# ODGIRON-v1_0-F4x1-0412.net
KiCad netlist of a schematic drawn in EAGLE
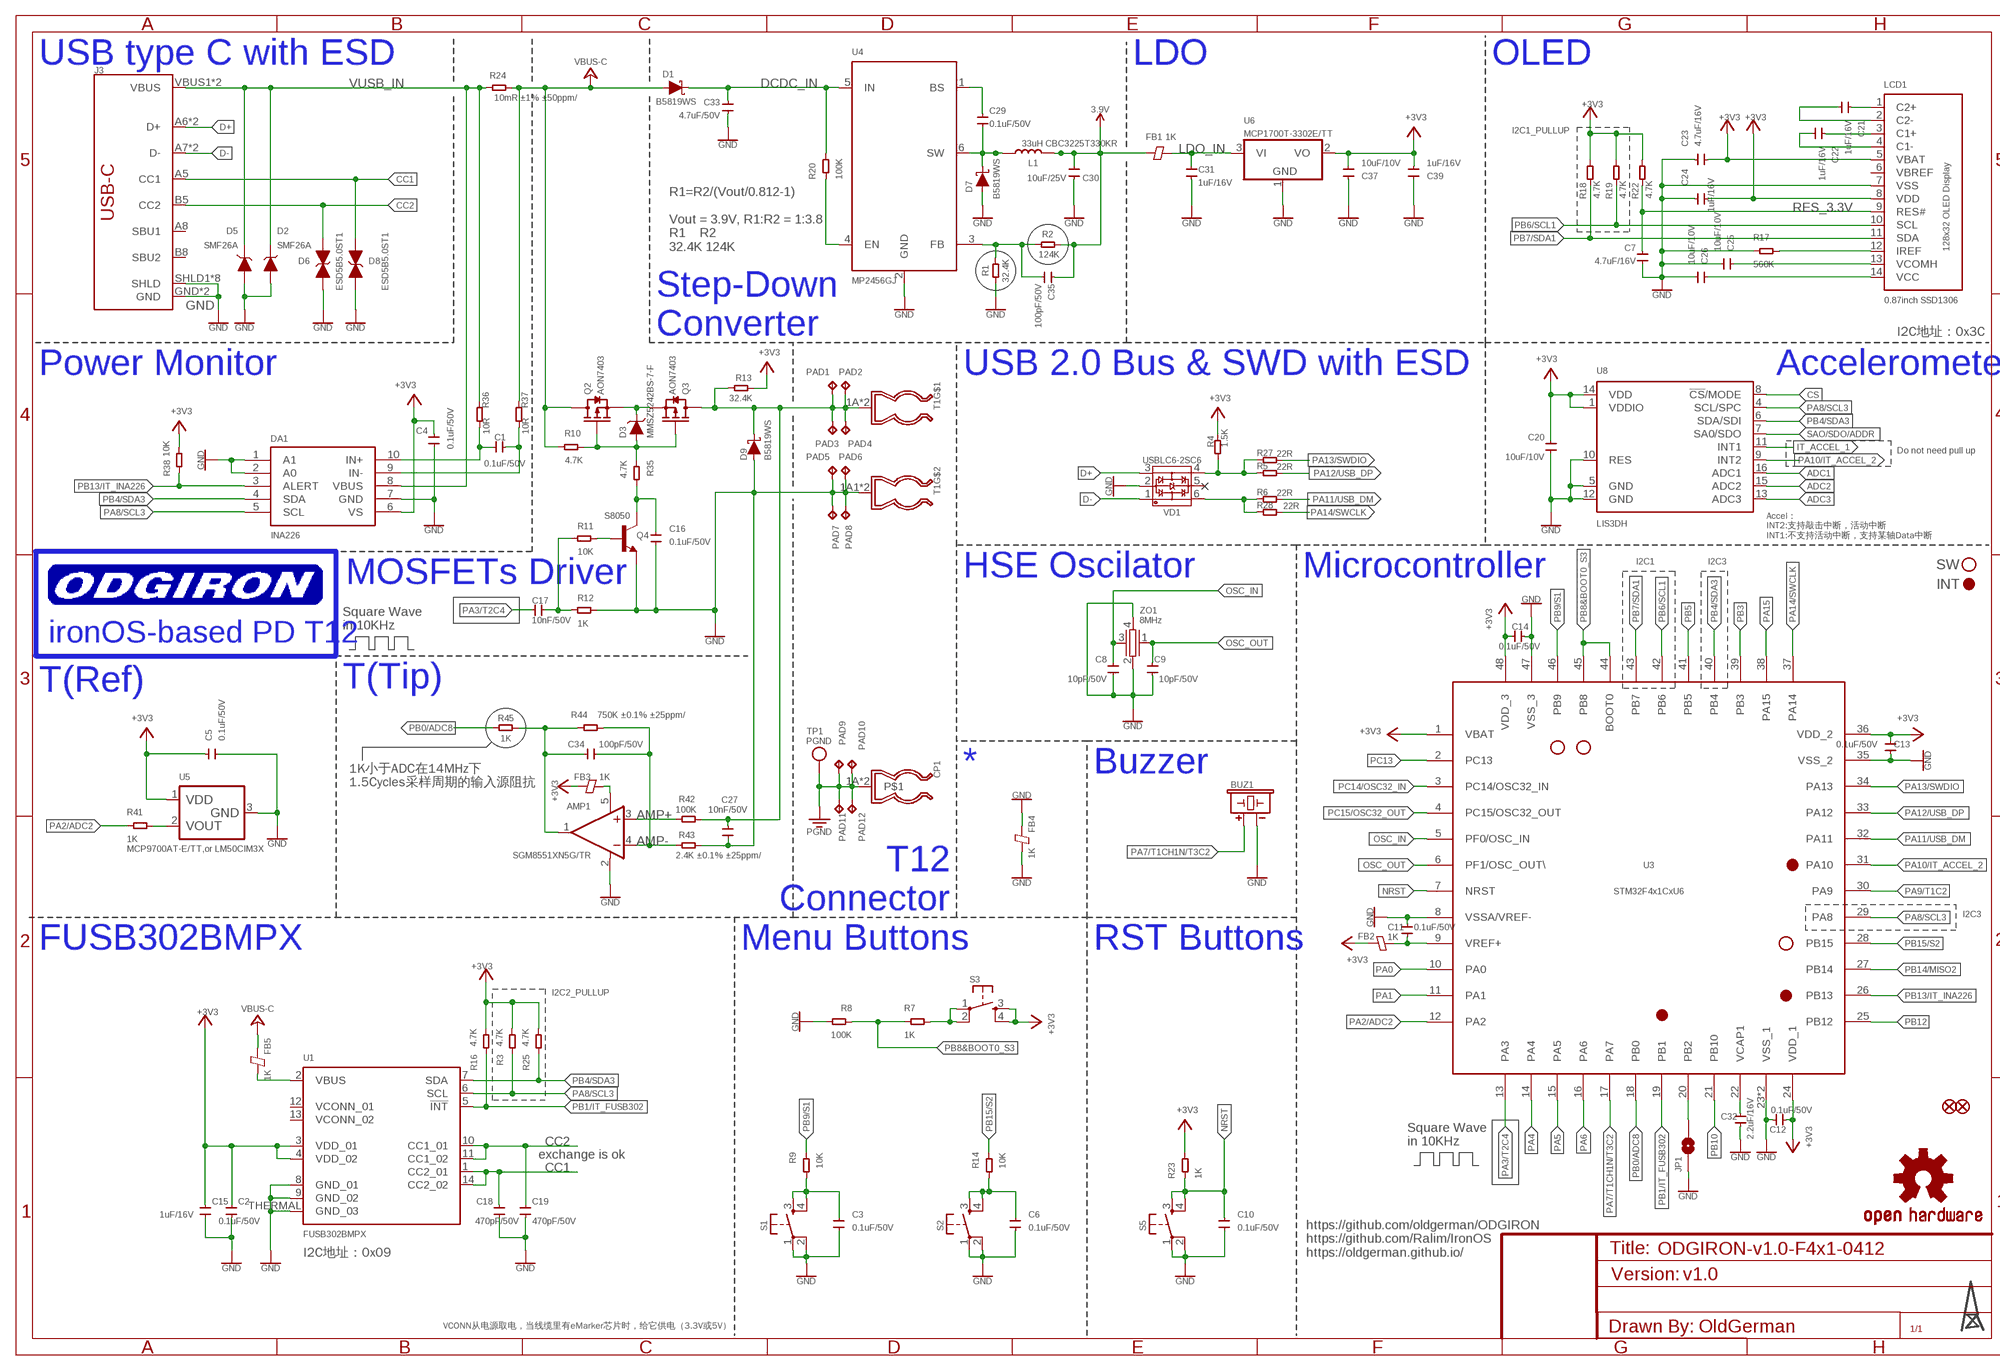
[diagram p0: schematic, sheet 1, part 1 of 2]
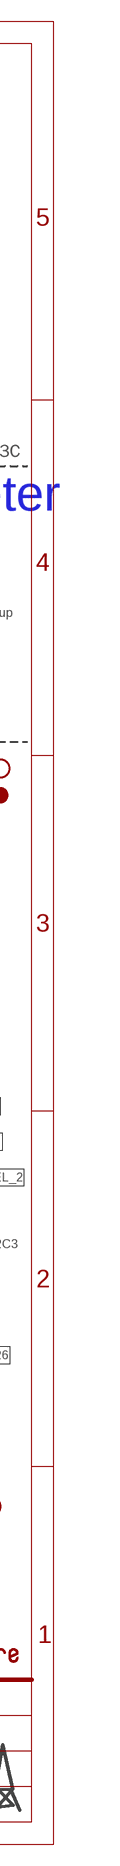
[diagram p1: schematic, sheet 1, part 2 of 2]

(export (version "E")
  (design (tool "Eeschema 10.0.6"))
  (components
    (comp (ref "AMP1")
      (value "SGM8551XN5G/TR")
      (footprint "eagle-import:SOT23-5")
      (fields (field (name "MPN") "OPA340NA/3KG4"))
      (libsource (lib "eagle-import") (part "AMP_SIMGLEN"))
    )
    (comp (ref "BUZ1")
      (value "BUZZERBUZZER_5020")
      (footprint "eagle-import:BUZZER_5020")
      (libsource (lib "eagle-import") (part "BUZZERBUZZER_5020"))
    )
    (comp (ref "C1")
      (value "0.1uF/50V")
      (footprint "eagle-import:C0603")
      (libsource (lib "eagle-import") (part "SEEED_CAP-0603"))
    )
    (comp (ref "C2")
      (value "0.1uF/50V")
      (footprint "eagle-import:C0603")
      (libsource (lib "eagle-import") (part "SEEED_CAP-0603"))
    )
    (comp (ref "C3")
      (value "0.1uF/50V")
      (footprint "eagle-import:C0603")
      (libsource (lib "eagle-import") (part "SEEED_CAP-0603"))
    )
    (comp (ref "C4")
      (value "0.1uF/50V")
      (footprint "eagle-import:C0603")
      (libsource (lib "eagle-import") (part "SEEED_CAP-0603"))
    )
    (comp (ref "C5")
      (value "0.1uF/50V")
      (footprint "eagle-import:C0603")
      (libsource (lib "eagle-import") (part "SEEED_CAP-0603"))
    )
    (comp (ref "C6")
      (value "0.1uF/50V")
      (footprint "eagle-import:C0603")
      (libsource (lib "eagle-import") (part "SEEED_CAP-0603"))
    )
    (comp (ref "C7")
      (value "4.7uF/16V")
      (footprint "eagle-import:C0603")
      (libsource (lib "eagle-import") (part "SEEED_CAP-0603"))
    )
    (comp (ref "C8")
      (value "10pF/50V")
      (footprint "eagle-import:C0603")
      (libsource (lib "eagle-import") (part "SEEED_CAP-0603"))
    )
    (comp (ref "C9")
      (value "10pF/50V")
      (footprint "eagle-import:C0603")
      (libsource (lib "eagle-import") (part "SEEED_CAP-0603"))
    )
    (comp (ref "C10")
      (value "0.1uF/50V")
      (footprint "eagle-import:C0603")
      (libsource (lib "eagle-import") (part "SEEED_CAP-0603"))
    )
    (comp (ref "C11")
      (value "0.1uF/50V")
      (footprint "eagle-import:C0603")
      (libsource (lib "eagle-import") (part "SEEED_CAP-0603"))
    )
    (comp (ref "C12")
      (value "0.1uF/50V")
      (footprint "eagle-import:C0603")
      (libsource (lib "eagle-import") (part "SEEED_CAP-0603"))
    )
    (comp (ref "C13")
      (value "0.1uF/50V")
      (footprint "eagle-import:C0603")
      (libsource (lib "eagle-import") (part "SEEED_CAP-0603"))
    )
    (comp (ref "C14")
      (value "0.1uF/50V")
      (footprint "eagle-import:C0603")
      (libsource (lib "eagle-import") (part "SEEED_CAP-0603"))
    )
    (comp (ref "C15")
      (value "1uF/16V")
      (footprint "eagle-import:C0603")
      (libsource (lib "eagle-import") (part "SEEED_CAP-0603"))
    )
    (comp (ref "C16")
      (value "0.1uF/50V")
      (footprint "eagle-import:C0603")
      (libsource (lib "eagle-import") (part "SEEED_CAP-0603"))
    )
    (comp (ref "C17")
      (value "10nF/50V")
      (footprint "eagle-import:C0603")
      (libsource (lib "eagle-import") (part "SEEED_CAP-0603"))
    )
    (comp (ref "C18")
      (value "470pF/50V")
      (footprint "eagle-import:C0603")
      (libsource (lib "eagle-import") (part "SEEED_CAP-0603"))
    )
    (comp (ref "C19")
      (value "470pF/50V")
      (footprint "eagle-import:C0603")
      (libsource (lib "eagle-import") (part "SEEED_CAP-0603"))
    )
    (comp (ref "C20")
      (value "10uF/10V")
      (footprint "eagle-import:C0603")
      (libsource (lib "eagle-import") (part "SEEED_CAP-0603"))
    )
    (comp (ref "C21")
      (value "1uF/16V")
      (footprint "eagle-import:C0603")
      (libsource (lib "eagle-import") (part "SEEED_CAP-0603"))
    )
    (comp (ref "C22")
      (value "1uF/16V")
      (footprint "eagle-import:C0603")
      (libsource (lib "eagle-import") (part "SEEED_CAP-0603"))
    )
    (comp (ref "C23")
      (value "4.7uF/16V")
      (footprint "eagle-import:C0603")
      (libsource (lib "eagle-import") (part "SEEED_CAP-0603"))
    )
    (comp (ref "C24")
      (value "1uF/16V")
      (footprint "eagle-import:C0603")
      (libsource (lib "eagle-import") (part "SEEED_CAP-0603"))
    )
    (comp (ref "C25")
      (value "10uF/10V")
      (footprint "eagle-import:C0603")
      (libsource (lib "eagle-import") (part "SEEED_CAP-0603"))
    )
    (comp (ref "C26")
      (value "10uF/10V")
      (footprint "eagle-import:C0603")
      (libsource (lib "eagle-import") (part "SEEED_CAP-0603"))
    )
    (comp (ref "C27")
      (value "10nF/50V")
      (footprint "eagle-import:C0603")
      (libsource (lib "eagle-import") (part "SEEED_CAP-0603"))
    )
    (comp (ref "C29")
      (value "0.1uF/50V")
      (footprint "eagle-import:C0603")
      (libsource (lib "eagle-import") (part "SEEED_CAP-0603"))
    )
    (comp (ref "C30")
      (value "10uF/25V")
      (footprint "eagle-import:C0805")
      (libsource (lib "eagle-import") (part "SEEED_CAP-0805"))
    )
    (comp (ref "C31")
      (value "1uF/16V")
      (footprint "eagle-import:C0603")
      (libsource (lib "eagle-import") (part "SEEED_CAP-0603"))
    )
    (comp (ref "C32")
      (value "2.2uF/16V")
      (footprint "eagle-import:C0603")
      (libsource (lib "eagle-import") (part "SEEED_CAP-0603"))
    )
    (comp (ref "C33")
      (value "4.7uF/50V")
      (footprint "eagle-import:C0805")
      (libsource (lib "eagle-import") (part "SEEED_CAP-0805"))
    )
    (comp (ref "C34")
      (value "100pF/50V")
      (footprint "eagle-import:C0603")
      (libsource (lib "eagle-import") (part "SEEED_CAP-0603"))
    )
    (comp (ref "C35")
      (value "100pF/50V")
      (footprint "eagle-import:C0603")
      (libsource (lib "eagle-import") (part "SEEED_CAP-0603"))
    )
    (comp (ref "C37")
      (value "10uF/10V")
      (footprint "eagle-import:C0603")
      (libsource (lib "eagle-import") (part "SEEED_CAP-0603"))
    )
    (comp (ref "C39")
      (value "1uF/16V")
      (footprint "eagle-import:C0603")
      (libsource (lib "eagle-import") (part "SEEED_CAP-0603"))
    )
    (comp (ref "CP1")
      (value "FUSE_CLIPS_01")
      (footprint "eagle-import:FUSE_CLIPS_01")
      (libsource (lib "eagle-import") (part "FUSE_CLIPS_01"))
    )
    (comp (ref "D1")
      (value "B5819WS")
      (footprint "eagle-import:SOD-323")
      (libsource (lib "eagle-import") (part "DIODE_SCHOTTKYSOD323"))
    )
    (comp (ref "D2")
      (value "SMF26A")
      (footprint "eagle-import:SOD-123")
      (libsource (lib "eagle-import") (part "DIODE-TVS_UNIDIRECTIONALSOD-123"))
    )
    (comp (ref "D3")
      (value "MMSZ5242BS-7-F")
      (footprint "eagle-import:SOD-323")
      (libsource (lib "eagle-import") (part "DIODE_ZENERSOD-323"))
    )
    (comp (ref "D5")
      (value "SMF26A")
      (footprint "eagle-import:SOD-123")
      (libsource (lib "eagle-import") (part "DIODE-TVS_UNIDIRECTIONALSOD-123"))
    )
    (comp (ref "D6")
      (value "ESD5B5.0ST1")
      (footprint "eagle-import:SOD-523")
      (libsource (lib "eagle-import") (part "DIODE-TVS_BI−DIRECTIONALSOD-523"))
    )
    (comp (ref "D7")
      (value "B5819WS")
      (footprint "eagle-import:SOD-323")
      (libsource (lib "eagle-import") (part "DIODE_SCHOTTKYSOD323"))
    )
    (comp (ref "D8")
      (value "ESD5B5.0ST1")
      (footprint "eagle-import:SOD-523")
      (libsource (lib "eagle-import") (part "DIODE-TVS_BI−DIRECTIONALSOD-523"))
    )
    (comp (ref "D9")
      (value "B5819WS")
      (footprint "eagle-import:SOD-323")
      (libsource (lib "eagle-import") (part "DIODE_SCHOTTKYSOD323"))
    )
    (comp (ref "DA1")
      (value "INA226")
      (footprint "eagle-import:MSOP10")
      (libsource (lib "eagle-import") (part "INA226"))
    )
    (comp (ref "FB1")
      (value "1K")
      (footprint "eagle-import:F0603")
      (libsource (lib "eagle-import") (part "FERRITE-BEAD-0603"))
    )
    (comp (ref "FB2")
      (value "1K")
      (footprint "eagle-import:F0603")
      (libsource (lib "eagle-import") (part "FERRITE-BEAD-0603"))
    )
    (comp (ref "FB3")
      (value "1K")
      (footprint "eagle-import:F0603")
      (libsource (lib "eagle-import") (part "FERRITE-BEAD-0603"))
    )
    (comp (ref "FB4")
      (value "1K")
      (footprint "eagle-import:F0603")
      (libsource (lib "eagle-import") (part "FERRITE-BEAD-0603"))
    )
    (comp (ref "FB5")
      (value "1K")
      (footprint "eagle-import:F0603")
      (libsource (lib "eagle-import") (part "FERRITE-BEAD-0603"))
    )
    (comp (ref "FID1")
      (value "FIDUCIAL")
      (footprint "eagle-import:FIDUCIAL_1MM")
      (libsource (lib "eagle-import") (part "FIDUCIAL"))
    )
    (comp (ref "FID2")
      (value "FIDUCIAL")
      (footprint "eagle-import:FIDUCIAL_1MM")
      (libsource (lib "eagle-import") (part "FIDUCIAL"))
    )
    (comp (ref "J3")
      (value "USB_C_LONG-SYMBOL2-LAYER")
      (footprint "eagle-import:USB-C-16P")
      (libsource (lib "eagle-import") (part "USB_C_LONG-SYMBOL2-LAYER"))
    )
    (comp (ref "JP1")
      (value "JUMPER-SMT_2_NO_SILK")
      (footprint "eagle-import:SMT-JUMPER_2_NO_SILK")
      (libsource (lib "eagle-import") (part "JUMPER-SMT_2_NO_SILK"))
    )
    (comp (ref "L1")
      (value "33uH CBC3225T330KR")
      (footprint "eagle-import:SMD,3.2X2.5X2.5MM")
      (libsource (lib "eagle-import") (part "INDUCTOR3225"))
    )
    (comp (ref "LCD1")
      (value "0.87inch SSD1306")
      (footprint "eagle-import:0.87INCH_128X32_OLED_SSD1306")
      (libsource (lib "eagle-import") (part "0.87INCH_OLED_128X32_SSD1306"))
    )
    (comp (ref "LOGO1")
      (value "OSHW-LOGONO_SILK")
      (footprint "eagle-import:DUMMY")
      (libsource (lib "eagle-import") (part "OSHW-LOGONO_SILK"))
    )
    (comp (ref "PAD1")
      (value "PADTP16SQ")
      (footprint "eagle-import:TP16SQ")
      (libsource (lib "eagle-import") (part "PADTP16SQ"))
    )
    (comp (ref "PAD2")
      (value "PADTP16SQ")
      (footprint "eagle-import:TP16SQ")
      (libsource (lib "eagle-import") (part "PADTP16SQ"))
    )
    (comp (ref "PAD3")
      (value "PADTP16SQ")
      (footprint "eagle-import:TP16SQ")
      (libsource (lib "eagle-import") (part "PADTP16SQ"))
    )
    (comp (ref "PAD4")
      (value "PADTP16SQ")
      (footprint "eagle-import:TP16SQ")
      (libsource (lib "eagle-import") (part "PADTP16SQ"))
    )
    (comp (ref "PAD5")
      (value "PADTP16SQ")
      (footprint "eagle-import:TP16SQ")
      (libsource (lib "eagle-import") (part "PADTP16SQ"))
    )
    (comp (ref "PAD6")
      (value "PADTP16SQ")
      (footprint "eagle-import:TP16SQ")
      (libsource (lib "eagle-import") (part "PADTP16SQ"))
    )
    (comp (ref "PAD7")
      (value "PADTP16SQ")
      (footprint "eagle-import:TP16SQ")
      (libsource (lib "eagle-import") (part "PADTP16SQ"))
    )
    (comp (ref "PAD8")
      (value "PADTP16SQ")
      (footprint "eagle-import:TP16SQ")
      (libsource (lib "eagle-import") (part "PADTP16SQ"))
    )
    (comp (ref "PAD9")
      (value "PADTP16SQ")
      (footprint "eagle-import:TP16SQ")
      (libsource (lib "eagle-import") (part "PADTP16SQ"))
    )
    (comp (ref "PAD10")
      (value "PADTP16SQ")
      (footprint "eagle-import:TP16SQ")
      (libsource (lib "eagle-import") (part "PADTP16SQ"))
    )
    (comp (ref "PAD11")
      (value "PADTP16SQ")
      (footprint "eagle-import:TP16SQ")
      (libsource (lib "eagle-import") (part "PADTP16SQ"))
    )
    (comp (ref "PAD12")
      (value "PADTP16SQ")
      (footprint "eagle-import:TP16SQ")
      (libsource (lib "eagle-import") (part "PADTP16SQ"))
    )
    (comp (ref "Q2")
      (value "AON7403")
      (footprint "eagle-import:DFN8P-0.65-3X3X0.8MM")
      (libsource (lib "eagle-import") (part "MOSFET-P-AON7403"))
    )
    (comp (ref "Q3")
      (value "AON7403")
      (footprint "eagle-import:DFN8P-0.65-3X3X0.8MM")
      (libsource (lib "eagle-import") (part "MOSFET-P-AON7403"))
    )
    (comp (ref "Q4")
      (value "S8050")
      (footprint "eagle-import:SOT23-3")
      (libsource (lib "eagle-import") (part "TRANS_NPN-MMBT2222AL"))
    )
    (comp (ref "R1")
      (value "32.4K")
      (footprint "eagle-import:R0603")
      (libsource (lib "eagle-import") (part "SEEED_RES-0603"))
    )
    (comp (ref "R2")
      (value "124K")
      (footprint "eagle-import:R0603")
      (libsource (lib "eagle-import") (part "SEEED_RES-0603"))
    )
    (comp (ref "R3")
      (value "4.7K")
      (footprint "eagle-import:R0603")
      (libsource (lib "eagle-import") (part "SEEED_RES-0603"))
    )
    (comp (ref "R4")
      (value "1.5K")
      (footprint "eagle-import:R0603")
      (libsource (lib "eagle-import") (part "SEEED_RES-0603"))
    )
    (comp (ref "R5")
      (value "22R")
      (footprint "eagle-import:R0603")
      (libsource (lib "eagle-import") (part "SEEED_RES-0603"))
    )
    (comp (ref "R6")
      (value "22R")
      (footprint "eagle-import:R0603")
      (libsource (lib "eagle-import") (part "SEEED_RES-0603"))
    )
    (comp (ref "R7")
      (value "1K")
      (footprint "eagle-import:R0603")
      (libsource (lib "eagle-import") (part "SEEED_RES-0603"))
    )
    (comp (ref "R8")
      (value "100K")
      (footprint "eagle-import:R0603")
      (libsource (lib "eagle-import") (part "SEEED_RES-0603"))
    )
    (comp (ref "R9")
      (value "10K")
      (footprint "eagle-import:R0603")
      (libsource (lib "eagle-import") (part "SEEED_RES-0603"))
    )
    (comp (ref "R10")
      (value "4.7K")
      (footprint "eagle-import:R0603")
      (libsource (lib "eagle-import") (part "SEEED_RES-0603"))
    )
    (comp (ref "R11")
      (value "10K")
      (footprint "eagle-import:R0603")
      (libsource (lib "eagle-import") (part "SEEED_RES-0603"))
    )
    (comp (ref "R12")
      (value "1K")
      (footprint "eagle-import:R0603")
      (libsource (lib "eagle-import") (part "SEEED_RES-0603"))
    )
    (comp (ref "R13")
      (value "32.4K")
      (footprint "eagle-import:R0603")
      (libsource (lib "eagle-import") (part "SEEED_RES-0603"))
    )
    (comp (ref "R14")
      (value "10K")
      (footprint "eagle-import:R0603")
      (libsource (lib "eagle-import") (part "SEEED_RES-0603"))
    )
    (comp (ref "R16")
      (value "4.7K")
      (footprint "eagle-import:R0603")
      (libsource (lib "eagle-import") (part "SEEED_RES-0603"))
    )
    (comp (ref "R17")
      (value "560K")
      (footprint "eagle-import:R0603")
      (libsource (lib "eagle-import") (part "SEEED_RES-0603"))
    )
    (comp (ref "R18")
      (value "4.7K")
      (footprint "eagle-import:R0603")
      (libsource (lib "eagle-import") (part "SEEED_RES-0603"))
    )
    (comp (ref "R19")
      (value "4.7K")
      (footprint "eagle-import:R0603")
      (libsource (lib "eagle-import") (part "SEEED_RES-0603"))
    )
    (comp (ref "R20")
      (value "100K")
      (footprint "eagle-import:R0603")
      (libsource (lib "eagle-import") (part "SEEED_RES-0603"))
    )
    (comp (ref "R22")
      (value "4.7K")
      (footprint "eagle-import:R0603")
      (libsource (lib "eagle-import") (part "SEEED_RES-0603"))
    )
    (comp (ref "R23")
      (value "1K")
      (footprint "eagle-import:R0603")
      (libsource (lib "eagle-import") (part "SEEED_RES-0603"))
    )
    (comp (ref "R24")
      (value "10mR ±1% ±50ppm/℃")
      (footprint "eagle-import:R1206")
      (libsource (lib "eagle-import") (part "SEEED_RES-1206"))
    )
    (comp (ref "R25")
      (value "4.7K")
      (footprint "eagle-import:R0603")
      (libsource (lib "eagle-import") (part "SEEED_RES-0603"))
    )
    (comp (ref "R27")
      (value "22R")
      (footprint "eagle-import:R0603")
      (libsource (lib "eagle-import") (part "SEEED_RES-0603"))
    )
    (comp (ref "R28")
      (value "22R")
      (footprint "eagle-import:R0603")
      (libsource (lib "eagle-import") (part "SEEED_RES-0603"))
    )
    (comp (ref "R35")
      (value "4.7K")
      (footprint "eagle-import:R0603")
      (libsource (lib "eagle-import") (part "SEEED_RES-0603"))
    )
    (comp (ref "R36")
      (value "10R")
      (footprint "eagle-import:R0603")
      (libsource (lib "eagle-import") (part "SEEED_RES-0603"))
    )
    (comp (ref "R37")
      (value "10R")
      (footprint "eagle-import:R0603")
      (libsource (lib "eagle-import") (part "SEEED_RES-0603"))
    )
    (comp (ref "R38")
      (value "10K")
      (footprint "eagle-import:R0603")
      (libsource (lib "eagle-import") (part "SEEED_RES-0603"))
    )
    (comp (ref "R41")
      (value "1K")
      (footprint "eagle-import:R0603")
      (libsource (lib "eagle-import") (part "SEEED_RES-0603"))
    )
    (comp (ref "R42")
      (value "100K")
      (footprint "eagle-import:R0603")
      (libsource (lib "eagle-import") (part "SEEED_RES-0603"))
    )
    (comp (ref "R43")
      (value "2.4K ±0.1% ±25ppm/℃")
      (footprint "eagle-import:R0603")
      (libsource (lib "eagle-import") (part "SEEED_RES-0603"))
    )
    (comp (ref "R44")
      (value "750K ±0.1% ±25ppm/℃")
      (footprint "eagle-import:R0603")
      (libsource (lib "eagle-import") (part "SEEED_RES-0603"))
    )
    (comp (ref "R45")
      (value "1K")
      (footprint "eagle-import:R0603")
      (libsource (lib "eagle-import") (part "SEEED_RES-0603"))
    )
    (comp (ref "S1")
      (value "TAC_SWITCHSMD")
      (footprint "eagle-import:TACTILE_SWITCH_SMD")
      (libsource (lib "eagle-import") (part "TAC_SWITCHSMD"))
    )
    (comp (ref "S2")
      (value "TAC_SWITCHSMD")
      (footprint "eagle-import:TACTILE_SWITCH_SMD")
      (libsource (lib "eagle-import") (part "TAC_SWITCHSMD"))
    )
    (comp (ref "S3")
      (value "TAC_SWITCHSMD")
      (footprint "eagle-import:TACTILE_SWITCH_SMD")
      (libsource (lib "eagle-import") (part "TAC_SWITCHSMD"))
    )
    (comp (ref "S5")
      (value "TAC_SWITCHSMD")
      (footprint "eagle-import:TACTILE_SWITCH_SMD")
      (libsource (lib "eagle-import") (part "untitled_TAC_SWITCHSMD"))
    )
    (comp (ref "T1")
      (value "HAKKO_T12_K-TYPE_WITH_FUSE_CLIPS_X2")
      (footprint "eagle-import:HAKKO_T12_K-TYPE_WITH_FUSE_CLIPS_X2")
      (libsource (lib "eagle-import") (part "HAKKO_T12_K-TYPE_WITH_FUSE_CLIPS_X2"))
    )
    (comp (ref "TP1")
      (value "PGND")
      (footprint "eagle-import:TESTPOINT_ROUND_2MM")
      (libsource (lib "eagle-import") (part "TESTPOINTROUND2MM"))
    )
    (comp (ref "U1")
      (value "FUSB302BMPX")
      (footprint "eagle-import:QFN14-2.5X2.5MM")
      (libsource (lib "eagle-import") (part "FUSB302"))
    )
    (comp (ref "U3")
      (value "STM32F4x1CxU6")
      (footprint "eagle-import:QFN48_7X7MM_0.5MM")
      (libsource (lib "eagle-import") (part "STM32F4_QFN48"))
    )
    (comp (ref "U4")
      (value "MP2456GJ")
      (footprint "eagle-import:SOT23-6")
      (libsource (lib "eagle-import") (part "MP2456"))
    )
    (comp (ref "U5")
      (value "MCP9700AT-E/TT,or LM50CIM3X")
      (footprint "eagle-import:SOT23-3@1")
      (libsource (lib "eagle-import") (part "MCP9700"))
    )
    (comp (ref "U6")
      (value "MCP1700T-3302E/TT")
      (footprint "eagle-import:SOT23-3")
      (libsource (lib "eagle-import") (part "MCP1700"))
    )
    (comp (ref "U8")
      (value "LIS3DH")
      (footprint "eagle-import:LGA-16-3X3")
      (libsource (lib "eagle-import") (part "LIS3DH"))
    )
    (comp (ref "VD1")
      (value "USBLC6-2SC6")
      (footprint "eagle-import:SOT23-6")
      (libsource (lib "eagle-import") (part "USBLC6-2SOT23-6"))
    )
    (comp (ref "ZO1")
      (value "8MHz")
      (footprint "eagle-import:3.2X2.5_KX-7")
      (libsource (lib "eagle-import") (part "3225_CRYSTALL"))
    )
  )
  (nets
    (net (code "1") (name "+3V3") (class "Default")
      (node (ref "C12") (pin "2") (pinfunction "P$2_2") (pintype "passive"))
      (node (ref "C13") (pin "2") (pinfunction "P$2_2") (pintype "passive"))
      (node (ref "C14") (pin "2") (pinfunction "P$2_2") (pintype "passive"))
      (node (ref "C15") (pin "1") (pinfunction "P$1_1") (pintype "passive"))
      (node (ref "C2") (pin "1") (pinfunction "P$1_1") (pintype "passive"))
      (node (ref "C20") (pin "2") (pinfunction "P$2_2") (pintype "passive"))
      (node (ref "C23") (pin "2") (pinfunction "P$2_2") (pintype "passive"))
      (node (ref "C24") (pin "2") (pinfunction "P$2_2") (pintype "passive"))
      (node (ref "C37") (pin "2") (pinfunction "P$2_2") (pintype "passive"))
      (node (ref "C39") (pin "2") (pinfunction "P$2_2") (pintype "passive"))
      (node (ref "C4") (pin "1") (pinfunction "P$1_1") (pintype "passive"))
      (node (ref "C5") (pin "1") (pinfunction "P$1_1") (pintype "passive"))
      (node (ref "DA1") (pin "6") (pinfunction "VS_6") (pintype "bidirectional"))
      (node (ref "FB2") (pin "2") (pinfunction "2_2") (pintype "bidirectional"))
      (node (ref "FB3") (pin "2") (pinfunction "2_2") (pintype "bidirectional"))
      (node (ref "LCD1") (pin "5") (pinfunction "VBAT_5") (pintype "power_in"))
      (node (ref "LCD1") (pin "8") (pinfunction "VDD_8") (pintype "power_in"))
      (node (ref "R13") (pin "2") (pinfunction "2_2") (pintype "passive"))
      (node (ref "R16") (pin "1") (pinfunction "1_1") (pintype "passive"))
      (node (ref "R18") (pin "2") (pinfunction "2_2") (pintype "passive"))
      (node (ref "R19") (pin "2") (pinfunction "2_2") (pintype "passive"))
      (node (ref "R22") (pin "2") (pinfunction "2_2") (pintype "passive"))
      (node (ref "R23") (pin "2") (pinfunction "2_2") (pintype "passive"))
      (node (ref "R25") (pin "1") (pinfunction "1_1") (pintype "passive"))
      (node (ref "R3") (pin "1") (pinfunction "1_1") (pintype "passive"))
      (node (ref "R38") (pin "1") (pinfunction "1_1") (pintype "passive"))
      (node (ref "R4") (pin "2") (pinfunction "2_2") (pintype "passive"))
      (node (ref "S3") (pin "3") (pinfunction "3_3") (pintype "passive"))
      (node (ref "S3") (pin "4") (pinfunction "4_4") (pintype "passive"))
      (node (ref "U1") (pin "3") (pinfunction "VDD_01_3") (pintype "bidirectional"))
      (node (ref "U1") (pin "4") (pinfunction "VDD_02_4") (pintype "bidirectional"))
      (node (ref "U3") (pin "1") (pinfunction "VBAT_1") (pintype "bidirectional"))
      (node (ref "U3") (pin "24") (pinfunction "VDD_1_24") (pintype "bidirectional"))
      (node (ref "U3") (pin "36") (pinfunction "VDD_2_36") (pintype "bidirectional"))
      (node (ref "U3") (pin "48") (pinfunction "VDD_3_48") (pintype "bidirectional"))
      (node (ref "U5") (pin "1") (pinfunction "VDD_1") (pintype "input"))
      (node (ref "U6") (pin "2") (pinfunction "VO_2") (pintype "passive"))
      (node (ref "U8") (pin "1") (pinfunction "VDDIO_1") (pintype "bidirectional"))
      (node (ref "U8") (pin "14") (pinfunction "VDD_14") (pintype "bidirectional"))
    )
    (net (code "2") (name "/AMP+") (class "Default")
      (node (ref "AMP1") (pin "3") (pinfunction "+IN_3") (pintype "input"))
      (node (ref "R42") (pin "1") (pinfunction "1_1") (pintype "passive"))
    )
    (net (code "3") (name "/AMP-") (class "Default")
      (node (ref "AMP1") (pin "4") (pinfunction "-IN_4") (pintype "input"))
      (node (ref "C34") (pin "2") (pinfunction "P$2_2") (pintype "passive"))
      (node (ref "R43") (pin "1") (pinfunction "1_1") (pintype "passive"))
      (node (ref "R44") (pin "2") (pinfunction "2_2") (pintype "passive"))
    )
    (net (code "4") (name "/DCDC_IN") (class "Default")
      (node (ref "C33") (pin "1") (pinfunction "P$1_1") (pintype "passive"))
      (node (ref "D1") (pin "C") (pinfunction "C_C") (pintype "passive"))
      (node (ref "R20") (pin "2") (pinfunction "2_2") (pintype "passive"))
      (node (ref "U4") (pin "5") (pinfunction "IN_5") (pintype "bidirectional"))
    )
    (net (code "5") (name "/LDO_IN") (class "Default")
      (node (ref "C31") (pin "2") (pinfunction "P$2_2") (pintype "passive"))
      (node (ref "FB1") (pin "2") (pinfunction "2_2") (pintype "bidirectional"))
      (node (ref "U6") (pin "3") (pinfunction "VI_3") (pintype "input"))
    )
    (net (code "6") (name "/RES_3.3V") (class "Default")
      (node (ref "C7") (pin "1") (pinfunction "P$1_1") (pintype "passive"))
      (node (ref "LCD1") (pin "9") (pinfunction "RES#_9") (pintype "bidirectional"))
      (node (ref "R22") (pin "1") (pinfunction "1_1") (pintype "passive"))
    )
    (net (code "7") (name "/VBREF") (class "Default")
      (node (ref "LCD1") (pin "6") (pinfunction "VBREF_6") (pintype "power_in"))
    )
    (net (code "8") (name "/VUSB_IN") (class "Default")
      (node (ref "D2") (pin "C") (pinfunction "K_C") (pintype "passive"))
      (node (ref "D5") (pin "C") (pinfunction "K_C") (pintype "passive"))
      (node (ref "DA1") (pin "8") (pinfunction "VBUS_8") (pintype "bidirectional"))
      (node (ref "J3") (pin "VBUS1") (pinfunction "VBUS_VBUS1") (pintype "bidirectional"))
      (node (ref "J3") (pin "VBUS2") (pinfunction "VBUS_VBUS2") (pintype "bidirectional"))
      (node (ref "R24") (pin "2") (pinfunction "2_2") (pintype "passive"))
      (node (ref "R36") (pin "2") (pinfunction "2_2") (pintype "passive"))
    )
    (net (code "9") (name "3.9V") (class "Default")
      (node (ref "C30") (pin "1") (pinfunction "P$1_1") (pintype "passive"))
      (node (ref "C35") (pin "1") (pinfunction "P$1_1") (pintype "passive"))
      (node (ref "FB1") (pin "1") (pinfunction "1_1") (pintype "bidirectional"))
      (node (ref "L1") (pin "2") (pinfunction "2_2") (pintype "passive"))
      (node (ref "R2") (pin "1") (pinfunction "1_1") (pintype "passive"))
    )
    (net (code "10") (name "ADC1") (class "Default")
      (node (ref "U8") (pin "16") (pinfunction "ADC1_16") (pintype "bidirectional"))
    )
    (net (code "11") (name "ADC2") (class "Default")
      (node (ref "U8") (pin "15") (pinfunction "ADC2_15") (pintype "bidirectional"))
    )
    (net (code "12") (name "ADC3") (class "Default")
      (node (ref "U8") (pin "13") (pinfunction "ADC3_13") (pintype "bidirectional"))
    )
    (net (code "13") (name "CC1") (class "Default")
      (node (ref "C18") (pin "1") (pinfunction "P$1_1") (pintype "passive"))
      (node (ref "D8") (pin "K") (pinfunction "C_K") (pintype "passive"))
      (node (ref "J3") (pin "A5") (pinfunction "CC1_A5") (pintype "bidirectional"))
      (node (ref "U1") (pin "1") (pinfunction "CC2_01_1") (pintype "bidirectional"))
      (node (ref "U1") (pin "14") (pinfunction "CC2_02_14") (pintype "bidirectional"))
    )
    (net (code "14") (name "CC2") (class "Default")
      (node (ref "C19") (pin "1") (pinfunction "P$1_1") (pintype "passive"))
      (node (ref "D6") (pin "K") (pinfunction "C_K") (pintype "passive"))
      (node (ref "J3") (pin "B5") (pinfunction "CC2_B5") (pintype "bidirectional"))
      (node (ref "U1") (pin "10") (pinfunction "CC1_01_10") (pintype "bidirectional"))
      (node (ref "U1") (pin "11") (pinfunction "CC1_02_11") (pintype "bidirectional"))
    )
    (net (code "15") (name "CS") (class "Default")
      (node (ref "U8") (pin "8") (pinfunction "~{CS}/MODE_8") (pintype "bidirectional"))
    )
    (net (code "16") (name "D+") (class "Default")
      (node (ref "J3") (pin "A6") (pinfunction "D+_A6") (pintype "bidirectional"))
      (node (ref "J3") (pin "B6") (pinfunction "D+_B6") (pintype "bidirectional"))
      (node (ref "VD1") (pin "3") (pinfunction "P$3_3") (pintype "bidirectional"))
    )
    (net (code "17") (name "D-") (class "Default")
      (node (ref "J3") (pin "A7") (pinfunction "D-_A7") (pintype "bidirectional"))
      (node (ref "J3") (pin "B7") (pinfunction "D-_B7") (pintype "bidirectional"))
      (node (ref "VD1") (pin "1") (pinfunction "P$1_1") (pintype "bidirectional"))
    )
    (net (code "18") (name "GND") (class "Default")
      (node (ref "AMP1") (pin "2") (pinfunction "V-_2") (pintype "power_in"))
      (node (ref "BUZ1") (pin "-") (pinfunction "LEAD-_-") (pintype "passive"))
      (node (ref "C10") (pin "2") (pinfunction "P$2_2") (pintype "passive"))
      (node (ref "C11") (pin "1") (pinfunction "P$1_1") (pintype "passive"))
      (node (ref "C12") (pin "1") (pinfunction "P$1_1") (pintype "passive"))
      (node (ref "C13") (pin "1") (pinfunction "P$1_1") (pintype "passive"))
      (node (ref "C14") (pin "1") (pinfunction "P$1_1") (pintype "passive"))
      (node (ref "C15") (pin "2") (pinfunction "P$2_2") (pintype "passive"))
      (node (ref "C16") (pin "1") (pinfunction "P$1_1") (pintype "passive"))
      (node (ref "C18") (pin "2") (pinfunction "P$2_2") (pintype "passive"))
      (node (ref "C19") (pin "2") (pinfunction "P$2_2") (pintype "passive"))
      (node (ref "C2") (pin "2") (pinfunction "P$2_2") (pintype "passive"))
      (node (ref "C20") (pin "1") (pinfunction "P$1_1") (pintype "passive"))
      (node (ref "C23") (pin "1") (pinfunction "P$1_1") (pintype "passive"))
      (node (ref "C24") (pin "1") (pinfunction "P$1_1") (pintype "passive"))
      (node (ref "C25") (pin "2") (pinfunction "P$2_2") (pintype "passive"))
      (node (ref "C26") (pin "2") (pinfunction "P$2_2") (pintype "passive"))
      (node (ref "C27") (pin "2") (pinfunction "P$2_2") (pintype "passive"))
      (node (ref "C3") (pin "2") (pinfunction "P$2_2") (pintype "passive"))
      (node (ref "C30") (pin "2") (pinfunction "P$2_2") (pintype "passive"))
      (node (ref "C31") (pin "1") (pinfunction "P$1_1") (pintype "passive"))
      (node (ref "C32") (pin "2") (pinfunction "P$2_2") (pintype "passive"))
      (node (ref "C33") (pin "2") (pinfunction "P$2_2") (pintype "passive"))
      (node (ref "C37") (pin "1") (pinfunction "P$1_1") (pintype "passive"))
      (node (ref "C39") (pin "1") (pinfunction "P$1_1") (pintype "passive"))
      (node (ref "C4") (pin "2") (pinfunction "P$2_2") (pintype "passive"))
      (node (ref "C5") (pin "2") (pinfunction "P$2_2") (pintype "passive"))
      (node (ref "C6") (pin "2") (pinfunction "P$2_2") (pintype "passive"))
      (node (ref "C7") (pin "2") (pinfunction "P$2_2") (pintype "passive"))
      (node (ref "C8") (pin "1") (pinfunction "P$1_1") (pintype "passive"))
      (node (ref "C9") (pin "1") (pinfunction "P$1_1") (pintype "passive"))
      (node (ref "D2") (pin "A") (pinfunction "A_A") (pintype "passive"))
      (node (ref "D5") (pin "A") (pinfunction "A_A") (pintype "passive"))
      (node (ref "D6") (pin "A") (pinfunction "A_A") (pintype "passive"))
      (node (ref "D7") (pin "A") (pinfunction "A_A") (pintype "passive"))
      (node (ref "D8") (pin "A") (pinfunction "A_A") (pintype "passive"))
      (node (ref "D9") (pin "A") (pinfunction "A_A") (pintype "passive"))
      (node (ref "DA1") (pin "1") (pinfunction "A1_1") (pintype "bidirectional"))
      (node (ref "DA1") (pin "2") (pinfunction "A0_2") (pintype "bidirectional"))
      (node (ref "DA1") (pin "7") (pinfunction "GND_7") (pintype "bidirectional"))
      (node (ref "FB4") (pin "1") (pinfunction "1_1") (pintype "bidirectional"))
      (node (ref "FB4") (pin "2") (pinfunction "2_2") (pintype "bidirectional"))
      (node (ref "J3") (pin "GND") (pinfunction "GND_GND") (pintype "bidirectional"))
      (node (ref "J3") (pin "GND2") (pinfunction "GND_GND2") (pintype "bidirectional"))
      (node (ref "J3") (pin "SHLD1") (pinfunction "SHLD_SHLD1") (pintype "bidirectional"))
      (node (ref "J3") (pin "SHLD2") (pinfunction "SHLD_SHLD2") (pintype "bidirectional"))
      (node (ref "J3") (pin "SHLD3") (pinfunction "SHLD_SHLD3") (pintype "bidirectional"))
      (node (ref "J3") (pin "SHLD4") (pinfunction "SHLD_SHLD4") (pintype "bidirectional"))
      (node (ref "J3") (pin "SHLD5") (pinfunction "SHLD_SHLD5") (pintype "bidirectional"))
      (node (ref "J3") (pin "SHLD6") (pinfunction "SHLD_SHLD6") (pintype "bidirectional"))
      (node (ref "J3") (pin "SHLD7") (pinfunction "SHLD_SHLD7") (pintype "bidirectional"))
      (node (ref "J3") (pin "SHLD8") (pinfunction "SHLD_SHLD8") (pintype "bidirectional"))
      (node (ref "JP1") (pin "1") (pinfunction "1_1") (pintype "passive"))
      (node (ref "LCD1") (pin "7") (pinfunction "VSS_7") (pintype "power_in"))
      (node (ref "PAD5") (pin "TP") (pinfunction "TP_TP") (pintype "input"))
      (node (ref "PAD6") (pin "TP") (pinfunction "TP_TP") (pintype "input"))
      (node (ref "PAD7") (pin "TP") (pinfunction "TP_TP") (pintype "input"))
      (node (ref "PAD8") (pin "TP") (pinfunction "TP_TP") (pintype "input"))
      (node (ref "Q4") (pin "2") (pinfunction "E_2") (pintype "passive"))
      (node (ref "R1") (pin "1") (pinfunction "1_1") (pintype "passive"))
      (node (ref "R12") (pin "1") (pinfunction "1_1") (pintype "passive"))
      (node (ref "R17") (pin "1") (pinfunction "1_1") (pintype "passive"))
      (node (ref "R43") (pin "2") (pinfunction "2_2") (pintype "passive"))
      (node (ref "R8") (pin "2") (pinfunction "2_2") (pintype "passive"))
      (node (ref "S1") (pin "1") (pinfunction "1_1") (pintype "passive"))
      (node (ref "S1") (pin "2") (pinfunction "2_2") (pintype "passive"))
      (node (ref "S2") (pin "1") (pinfunction "1_1") (pintype "passive"))
      (node (ref "S2") (pin "2") (pinfunction "2_2") (pintype "passive"))
      (node (ref "S5") (pin "1") (pinfunction "1_1") (pintype "passive"))
      (node (ref "S5") (pin "2") (pinfunction "2_2") (pintype "passive"))
      (node (ref "T1") (pin "1A1") (pinfunction "P$1_1A1") (pintype "bidirectional"))
      (node (ref "T1") (pin "1B1") (pinfunction "P$1_1B1") (pintype "bidirectional"))
      (node (ref "U1") (pin "8") (pinfunction "GND_01_8") (pintype "bidirectional"))
      (node (ref "U1") (pin "9") (pinfunction "GND_02_9") (pintype "bidirectional"))
      (node (ref "U1") (pin "THERMAL") (pinfunction "GND_03_THERMAL") (pintype "bidirectional"))
      (node (ref "U3") (pin "23") (pinfunction "VSS_1_23") (pintype "bidirectional"))
      (node (ref "U3") (pin "35") (pinfunction "VSS_2_35") (pintype "bidirectional"))
      (node (ref "U3") (pin "47") (pinfunction "VSS_3_47") (pintype "bidirectional"))
      (node (ref "U3") (pin "8") (pinfunction "VSSA/VREF-_8") (pintype "bidirectional"))
      (node (ref "U3") (pin "P$1") (pinfunction "VSS_1_P$1") (pintype "bidirectional"))
      (node (ref "U4") (pin "2") (pinfunction "GND_2") (pintype "bidirectional"))
      (node (ref "U5") (pin "3") (pinfunction "GND_3") (pintype "passive"))
      (node (ref "U6") (pin "1") (pinfunction "GND_1") (pintype "passive"))
      (node (ref "U8") (pin "10") (pinfunction "RES_10") (pintype "bidirectional"))
      (node (ref "U8") (pin "12") (pinfunction "GND_12") (pintype "bidirectional"))
      (node (ref "U8") (pin "5") (pinfunction "GND_5") (pintype "bidirectional"))
      (node (ref "VD1") (pin "2") (pinfunction "P$2_2") (pintype "bidirectional"))
      (node (ref "ZO1") (pin "2") (pinfunction "P$3_2") (pintype "power_in"))
      (node (ref "ZO1") (pin "4") (pinfunction "P$4_4") (pintype "power_in"))
    )
    (net (code "19") (name "IT_ACCEL_1") (class "Default")
      (node (ref "U8") (pin "11") (pinfunction "INT1_11") (pintype "bidirectional"))
    )
    (net (code "20") (name "NRST") (class "Default")
      (node (ref "C10") (pin "1") (pinfunction "P$1_1") (pintype "passive"))
      (node (ref "R23") (pin "1") (pinfunction "1_1") (pintype "passive"))
      (node (ref "S5") (pin "3") (pinfunction "3_3") (pintype "passive"))
      (node (ref "S5") (pin "4") (pinfunction "4_4") (pintype "passive"))
      (node (ref "U3") (pin "7") (pinfunction "NRST_7") (pintype "bidirectional"))
    )
    (net (code "21") (name "Net-(AMP1-OUT)") (class "Default")
      (node (ref "AMP1") (pin "1") (pinfunction "OUT_1") (pintype "output"))
      (node (ref "C34") (pin "1") (pinfunction "P$1_1") (pintype "passive"))
      (node (ref "R44") (pin "1") (pinfunction "1_1") (pintype "passive"))
      (node (ref "R45") (pin "2") (pinfunction "2_2") (pintype "passive"))
    )
    (net (code "22") (name "Net-(AMP1-V+)") (class "Default")
      (node (ref "AMP1") (pin "5") (pinfunction "V+_5") (pintype "power_in"))
      (node (ref "FB3") (pin "1") (pinfunction "1_1") (pintype "bidirectional"))
    )
    (net (code "23") (name "Net-(C1-P$1)") (class "Default")
      (node (ref "C1") (pin "1") (pinfunction "P$1_1") (pintype "passive"))
      (node (ref "DA1") (pin "10") (pinfunction "IN+_10") (pintype "bidirectional"))
      (node (ref "R36") (pin "1") (pinfunction "1_1") (pintype "passive"))
    )
    (net (code "24") (name "Net-(C1-P$2)") (class "Default")
      (node (ref "C1") (pin "2") (pinfunction "P$2_2") (pintype "passive"))
      (node (ref "DA1") (pin "9") (pinfunction "IN-_9") (pintype "bidirectional"))
      (node (ref "R37") (pin "1") (pinfunction "1_1") (pintype "passive"))
    )
    (net (code "25") (name "Net-(C3-P$1)") (class "Default")
      (node (ref "C3") (pin "1") (pinfunction "P$1_1") (pintype "passive"))
      (node (ref "R9") (pin "2") (pinfunction "2_2") (pintype "passive"))
      (node (ref "S1") (pin "3") (pinfunction "3_3") (pintype "passive"))
      (node (ref "S1") (pin "4") (pinfunction "4_4") (pintype "passive"))
    )
    (net (code "26") (name "Net-(C6-P$1)") (class "Default")
      (node (ref "C6") (pin "1") (pinfunction "P$1_1") (pintype "passive"))
      (node (ref "R14") (pin "2") (pinfunction "2_2") (pintype "passive"))
      (node (ref "S2") (pin "3") (pinfunction "3_3") (pintype "passive"))
      (node (ref "S2") (pin "4") (pinfunction "4_4") (pintype "passive"))
    )
    (net (code "27") (name "Net-(C11-P$2)") (class "Default")
      (node (ref "C11") (pin "2") (pinfunction "P$2_2") (pintype "passive"))
      (node (ref "FB2") (pin "1") (pinfunction "1_1") (pintype "bidirectional"))
      (node (ref "U3") (pin "9") (pinfunction "VREF+_9") (pintype "bidirectional"))
    )
    (net (code "28") (name "Net-(C16-P$2)") (class "Default")
      (node (ref "C16") (pin "2") (pinfunction "P$2_2") (pintype "passive"))
      (node (ref "Q4") (pin "3") (pinfunction "C_3") (pintype "passive"))
      (node (ref "R35") (pin "2") (pinfunction "2_2") (pintype "passive"))
    )
    (net (code "29") (name "Net-(C17-P$1)") (class "Default")
      (node (ref "C17") (pin "1") (pinfunction "P$1_1") (pintype "passive"))
      (node (ref "R11") (pin "2") (pinfunction "2_2") (pintype "passive"))
      (node (ref "R12") (pin "2") (pinfunction "2_2") (pintype "passive"))
    )
    (net (code "30") (name "Net-(C21-P$1)") (class "Default")
      (node (ref "C21") (pin "1") (pinfunction "P$1_1") (pintype "passive"))
      (node (ref "LCD1") (pin "1") (pinfunction "C2+_1") (pintype "bidirectional"))
    )
    (net (code "31") (name "Net-(C21-P$2)") (class "Default")
      (node (ref "C21") (pin "2") (pinfunction "P$2_2") (pintype "passive"))
      (node (ref "LCD1") (pin "2") (pinfunction "C2-_2") (pintype "bidirectional"))
    )
    (net (code "32") (name "Net-(C22-P$1)") (class "Default")
      (node (ref "C22") (pin "1") (pinfunction "P$1_1") (pintype "passive"))
      (node (ref "LCD1") (pin "3") (pinfunction "C1+_3") (pintype "bidirectional"))
    )
    (net (code "33") (name "Net-(C22-P$2)") (class "Default")
      (node (ref "C22") (pin "2") (pinfunction "P$2_2") (pintype "passive"))
      (node (ref "LCD1") (pin "4") (pinfunction "C1-_4") (pintype "bidirectional"))
    )
    (net (code "34") (name "Net-(C25-P$1)") (class "Default")
      (node (ref "C25") (pin "1") (pinfunction "P$1_1") (pintype "passive"))
      (node (ref "LCD1") (pin "13") (pinfunction "VCOMH_13") (pintype "power_in"))
    )
    (net (code "35") (name "Net-(C26-P$1)") (class "Default")
      (node (ref "C26") (pin "1") (pinfunction "P$1_1") (pintype "passive"))
      (node (ref "LCD1") (pin "14") (pinfunction "VCC_14") (pintype "power_in"))
    )
    (net (code "36") (name "Net-(C27-P$1)") (class "Default")
      (node (ref "C27") (pin "1") (pinfunction "P$1_1") (pintype "passive"))
      (node (ref "D9") (pin "C") (pinfunction "C_C") (pintype "passive"))
      (node (ref "PAD1") (pin "TP") (pinfunction "TP_TP") (pintype "input"))
      (node (ref "PAD2") (pin "TP") (pinfunction "TP_TP") (pintype "input"))
      (node (ref "PAD3") (pin "TP") (pinfunction "TP_TP") (pintype "input"))
      (node (ref "PAD4") (pin "TP") (pinfunction "TP_TP") (pintype "input"))
      (node (ref "Q3") (pin "5") (pinfunction "D_5") (pintype "passive"))
      (node (ref "Q3") (pin "6") (pinfunction "D_6") (pintype "passive"))
      (node (ref "Q3") (pin "7") (pinfunction "D_7") (pintype "passive"))
      (node (ref "Q3") (pin "8") (pinfunction "D_8") (pintype "passive"))
      (node (ref "Q3") (pin "9") (pinfunction "D_9") (pintype "passive"))
      (node (ref "R13") (pin "1") (pinfunction "1_1") (pintype "passive"))
      (node (ref "R42") (pin "2") (pinfunction "2_2") (pintype "passive"))
      (node (ref "T1") (pin "1A") (pinfunction "P$1_1A") (pintype "bidirectional"))
      (node (ref "T1") (pin "1B") (pinfunction "P$1_1B") (pintype "bidirectional"))
    )
    (net (code "37") (name "Net-(C29-P$1)") (class "Default")
      (node (ref "C29") (pin "1") (pinfunction "P$1_1") (pintype "passive"))
      (node (ref "U4") (pin "1") (pinfunction "BS_1") (pintype "bidirectional"))
    )
    (net (code "38") (name "Net-(C29-P$2)") (class "Default")
      (node (ref "C29") (pin "2") (pinfunction "P$2_2") (pintype "passive"))
      (node (ref "D7") (pin "C") (pinfunction "C_C") (pintype "passive"))
      (node (ref "L1") (pin "1") (pinfunction "1_1") (pintype "passive"))
      (node (ref "U4") (pin "6") (pinfunction "SW_6") (pintype "bidirectional"))
    )
    (net (code "39") (name "Net-(C32-P$1)") (class "Default")
      (node (ref "C32") (pin "1") (pinfunction "P$1_1") (pintype "passive"))
      (node (ref "U3") (pin "22") (pinfunction "VCAP1_22") (pintype "bidirectional"))
    )
    (net (code "40") (name "Net-(C35-P$2)") (class "Default")
      (node (ref "C35") (pin "2") (pinfunction "P$2_2") (pintype "passive"))
      (node (ref "R1") (pin "2") (pinfunction "2_2") (pintype "passive"))
      (node (ref "R2") (pin "2") (pinfunction "2_2") (pintype "passive"))
      (node (ref "U4") (pin "3") (pinfunction "FB_3") (pintype "bidirectional"))
    )
    (net (code "41") (name "Net-(D3-PadC)") (class "Default")
      (node (ref "D3") (pin "C") (pinfunction "C_C") (pintype "passive"))
      (node (ref "Q2") (pin "1") (pinfunction "S_1") (pintype "passive"))
      (node (ref "Q2") (pin "2") (pinfunction "S_2") (pintype "passive"))
      (node (ref "Q2") (pin "3") (pinfunction "S_3") (pintype "passive"))
      (node (ref "Q3") (pin "1") (pinfunction "S_1") (pintype "passive"))
      (node (ref "Q3") (pin "2") (pinfunction "S_2") (pintype "passive"))
      (node (ref "Q3") (pin "3") (pinfunction "S_3") (pintype "passive"))
    )
    (net (code "42") (name "Net-(LCD1-IREF)") (class "Default")
      (node (ref "LCD1") (pin "12") (pinfunction "IREF_12") (pintype "bidirectional"))
      (node (ref "R17") (pin "2") (pinfunction "2_2") (pintype "passive"))
    )
    (net (code "43") (name "Net-(Q2-G)") (class "Default")
      (node (ref "D3") (pin "A") (pinfunction "A_A") (pintype "passive"))
      (node (ref "Q2") (pin "4") (pinfunction "G_4") (pintype "passive"))
      (node (ref "Q3") (pin "4") (pinfunction "G_4") (pintype "passive"))
      (node (ref "R10") (pin "2") (pinfunction "2_2") (pintype "passive"))
      (node (ref "R35") (pin "1") (pinfunction "1_1") (pintype "passive"))
    )
    (net (code "44") (name "Net-(Q4-B)") (class "Default")
      (node (ref "Q4") (pin "1") (pinfunction "B_1") (pintype "passive"))
      (node (ref "R11") (pin "1") (pinfunction "1_1") (pintype "passive"))
    )
    (net (code "45") (name "Net-(R7-Pad2)") (class "Default")
      (node (ref "R7") (pin "2") (pinfunction "2_2") (pintype "passive"))
      (node (ref "S3") (pin "1") (pinfunction "1_1") (pintype "passive"))
      (node (ref "S3") (pin "2") (pinfunction "2_2") (pintype "passive"))
    )
    (net (code "46") (name "Net-(U1-VBUS)") (class "Default")
      (node (ref "FB5") (pin "1") (pinfunction "1_1") (pintype "bidirectional"))
      (node (ref "U1") (pin "2") (pinfunction "VBUS_2") (pintype "bidirectional"))
    )
    (net (code "47") (name "Net-(U3-PB2)") (class "Default")
      (node (ref "JP1") (pin "2") (pinfunction "2_2") (pintype "passive"))
      (node (ref "U3") (pin "20") (pinfunction "PB2_20") (pintype "bidirectional"))
    )
    (net (code "48") (name "Net-(U4-EN)") (class "Default")
      (node (ref "R20") (pin "1") (pinfunction "1_1") (pintype "passive"))
      (node (ref "U4") (pin "4") (pinfunction "EN_4") (pintype "bidirectional"))
    )
    (net (code "49") (name "Net-(U5-VOUT)") (class "Default")
      (node (ref "R41") (pin "2") (pinfunction "2_2") (pintype "passive"))
      (node (ref "U5") (pin "2") (pinfunction "VOUT_2") (pintype "input"))
    )
    (net (code "50") (name "Net-(VD1-P$4)") (class "Default")
      (node (ref "R27") (pin "1") (pinfunction "1_1") (pintype "passive"))
      (node (ref "R4") (pin "1") (pinfunction "1_1") (pintype "passive"))
      (node (ref "R5") (pin "1") (pinfunction "1_1") (pintype "passive"))
      (node (ref "VD1") (pin "4") (pinfunction "P$4_4") (pintype "bidirectional"))
    )
    (net (code "51") (name "Net-(VD1-P$6)") (class "Default")
      (node (ref "R28") (pin "1") (pinfunction "1_1") (pintype "passive"))
      (node (ref "R6") (pin "1") (pinfunction "1_1") (pintype "passive"))
      (node (ref "VD1") (pin "6") (pinfunction "P$6_6") (pintype "bidirectional"))
    )
    (net (code "52") (name "OSC_IN") (class "Default")
      (node (ref "C8") (pin "2") (pinfunction "P$2_2") (pintype "passive"))
      (node (ref "U3") (pin "5") (pinfunction "PF0/OSC_IN_5") (pintype "bidirectional"))
      (node (ref "ZO1") (pin "3") (pinfunction "P$2_3") (pintype "bidirectional"))
    )
    (net (code "53") (name "OSC_OUT") (class "Default")
      (node (ref "C9") (pin "2") (pinfunction "P$2_2") (pintype "passive"))
      (node (ref "U3") (pin "6") (pinfunction "PF1/OSC_OUT\\_6") (pintype "bidirectional"))
      (node (ref "ZO1") (pin "1") (pinfunction "P$1_1") (pintype "bidirectional"))
    )
    (net (code "54") (name "PA0") (class "Default")
      (node (ref "U3") (pin "10") (pinfunction "PA0_10") (pintype "bidirectional"))
    )
    (net (code "55") (name "PA1") (class "Default")
      (node (ref "U3") (pin "11") (pinfunction "PA1_11") (pintype "bidirectional"))
    )
    (net (code "56") (name "PA2{slash}ADC2") (class "Default")
      (node (ref "R41") (pin "1") (pinfunction "1_1") (pintype "passive"))
      (node (ref "U3") (pin "12") (pinfunction "PA2_12") (pintype "bidirectional"))
    )
    (net (code "57") (name "PA3{slash}T2C4") (class "Default")
      (node (ref "C17") (pin "2") (pinfunction "P$2_2") (pintype "passive"))
      (node (ref "U3") (pin "13") (pinfunction "PA3_13") (pintype "bidirectional"))
    )
    (net (code "58") (name "PA4") (class "Default")
      (node (ref "U3") (pin "14") (pinfunction "PA4_14") (pintype "bidirectional"))
    )
    (net (code "59") (name "PA5") (class "Default")
      (node (ref "U3") (pin "15") (pinfunction "PA5_15") (pintype "bidirectional"))
    )
    (net (code "60") (name "PA6") (class "Default")
      (node (ref "U3") (pin "16") (pinfunction "PA6_16") (pintype "bidirectional"))
    )
    (net (code "61") (name "PA7{slash}T1CH1N{slash}T3C2") (class "Default")
      (node (ref "BUZ1") (pin "+") (pinfunction "LEAD+_+") (pintype "passive"))
      (node (ref "U3") (pin "17") (pinfunction "PA7_17") (pintype "bidirectional"))
    )
    (net (code "62") (name "PA8{slash}SCL3") (class "Default")
      (node (ref "DA1") (pin "5") (pinfunction "SCL_5") (pintype "bidirectional"))
      (node (ref "R3") (pin "2") (pinfunction "2_2") (pintype "passive"))
      (node (ref "U1") (pin "6") (pinfunction "SCL_6") (pintype "bidirectional"))
      (node (ref "U3") (pin "29") (pinfunction "PA8_29") (pintype "bidirectional"))
      (node (ref "U8") (pin "4") (pinfunction "SCL/SPC_4") (pintype "bidirectional"))
    )
    (net (code "63") (name "PA9{slash}T1C2") (class "Default")
      (node (ref "U3") (pin "30") (pinfunction "PA9_30") (pintype "bidirectional"))
    )
    (net (code "64") (name "PA10{slash}IT_ACCEL_2") (class "Default")
      (node (ref "U3") (pin "31") (pinfunction "PA10_31") (pintype "bidirectional"))
      (node (ref "U8") (pin "9") (pinfunction "INT2_9") (pintype "bidirectional"))
    )
    (net (code "65") (name "PA11{slash}USB_DM") (class "Default")
      (node (ref "R6") (pin "2") (pinfunction "2_2") (pintype "passive"))
      (node (ref "U3") (pin "32") (pinfunction "PA11_32") (pintype "bidirectional"))
    )
    (net (code "66") (name "PA12{slash}USB_DP") (class "Default")
      (node (ref "R5") (pin "2") (pinfunction "2_2") (pintype "passive"))
      (node (ref "U3") (pin "33") (pinfunction "PA12_33") (pintype "bidirectional"))
    )
    (net (code "67") (name "PA13{slash}SWDIO") (class "Default")
      (node (ref "R27") (pin "2") (pinfunction "2_2") (pintype "passive"))
      (node (ref "U3") (pin "34") (pinfunction "PA13_34") (pintype "bidirectional"))
    )
    (net (code "68") (name "PA14{slash}SWCLK") (class "Default")
      (node (ref "R28") (pin "2") (pinfunction "2_2") (pintype "passive"))
      (node (ref "U3") (pin "37") (pinfunction "PA14_37") (pintype "bidirectional"))
    )
    (net (code "69") (name "PA15") (class "Default")
      (node (ref "U3") (pin "38") (pinfunction "PA15_38") (pintype "bidirectional"))
    )
    (net (code "70") (name "PB0{slash}ADC8") (class "Default")
      (node (ref "R45") (pin "1") (pinfunction "1_1") (pintype "passive"))
      (node (ref "U3") (pin "18") (pinfunction "PB0_18") (pintype "bidirectional"))
    )
    (net (code "71") (name "PB1{slash}IT_FUSB302") (class "Default")
      (node (ref "R16") (pin "2") (pinfunction "2_2") (pintype "passive"))
      (node (ref "U1") (pin "5") (pinfunction "~{INT}_5") (pintype "bidirectional"))
      (node (ref "U3") (pin "19") (pinfunction "PB1_19") (pintype "bidirectional"))
    )
    (net (code "72") (name "PB3") (class "Default")
      (node (ref "U3") (pin "39") (pinfunction "PB3_39") (pintype "bidirectional"))
    )
    (net (code "73") (name "PB4{slash}SDA3") (class "Default")
      (node (ref "DA1") (pin "4") (pinfunction "SDA_4") (pintype "bidirectional"))
      (node (ref "R25") (pin "2") (pinfunction "2_2") (pintype "passive"))
      (node (ref "U1") (pin "7") (pinfunction "SDA_7") (pintype "bidirectional"))
      (node (ref "U3") (pin "40") (pinfunction "PB4_40") (pintype "bidirectional"))
      (node (ref "U8") (pin "6") (pinfunction "SDA/SDI_6") (pintype "bidirectional"))
    )
    (net (code "74") (name "PB5") (class "Default")
      (node (ref "U3") (pin "41") (pinfunction "PB5_41") (pintype "bidirectional"))
    )
    (net (code "75") (name "PB6{slash}SCL1") (class "Default")
      (node (ref "LCD1") (pin "10") (pinfunction "SCL_10") (pintype "bidirectional"))
      (node (ref "R19") (pin "1") (pinfunction "1_1") (pintype "passive"))
      (node (ref "U3") (pin "42") (pinfunction "PB6_42") (pintype "bidirectional"))
    )
    (net (code "76") (name "PB7{slash}SDA1") (class "Default")
      (node (ref "LCD1") (pin "11") (pinfunction "SDA_11") (pintype "bidirectional"))
      (node (ref "R18") (pin "1") (pinfunction "1_1") (pintype "passive"))
      (node (ref "U3") (pin "43") (pinfunction "PB7_43") (pintype "bidirectional"))
    )
    (net (code "77") (name "PB8&BOOT0_S3") (class "Default")
      (node (ref "R7") (pin "1") (pinfunction "1_1") (pintype "passive"))
      (node (ref "R8") (pin "1") (pinfunction "1_1") (pintype "passive"))
      (node (ref "U3") (pin "44") (pinfunction "BOOT0_44") (pintype "bidirectional"))
      (node (ref "U3") (pin "45") (pinfunction "PB8_45") (pintype "bidirectional"))
    )
    (net (code "78") (name "PB9{slash}S1") (class "Default")
      (node (ref "R9") (pin "1") (pinfunction "1_1") (pintype "passive"))
      (node (ref "U3") (pin "46") (pinfunction "PB9_46") (pintype "bidirectional"))
    )
    (net (code "79") (name "PB10") (class "Default")
      (node (ref "U3") (pin "21") (pinfunction "PB10_21") (pintype "bidirectional"))
    )
    (net (code "80") (name "PB12") (class "Default")
      (node (ref "U3") (pin "25") (pinfunction "PB12_25") (pintype "bidirectional"))
    )
    (net (code "81") (name "PB13{slash}IT_INA226") (class "Default")
      (node (ref "DA1") (pin "3") (pinfunction "ALERT_3") (pintype "bidirectional"))
      (node (ref "R38") (pin "2") (pinfunction "2_2") (pintype "passive"))
      (node (ref "U3") (pin "26") (pinfunction "PB13_26") (pintype "bidirectional"))
    )
    (net (code "82") (name "PB14{slash}MISO2") (class "Default")
      (node (ref "U3") (pin "27") (pinfunction "PB14_27") (pintype "bidirectional"))
    )
    (net (code "83") (name "PB15{slash}S2") (class "Default")
      (node (ref "R14") (pin "1") (pinfunction "1_1") (pintype "passive"))
      (node (ref "U3") (pin "28") (pinfunction "PB15_28") (pintype "bidirectional"))
    )
    (net (code "84") (name "PC13") (class "Default")
      (node (ref "U3") (pin "2") (pinfunction "PC13_2") (pintype "bidirectional"))
    )
    (net (code "85") (name "PC14{slash}OSC32_IN") (class "Default")
      (node (ref "U3") (pin "3") (pinfunction "PC14/OSC32_IN_3") (pintype "bidirectional"))
    )
    (net (code "86") (name "PC15{slash}OSC32_OUT") (class "Default")
      (node (ref "U3") (pin "4") (pinfunction "PC15/OSC32_OUT_4") (pintype "bidirectional"))
    )
    (net (code "87") (name "PGND") (class "Default")
      (node (ref "CP1") (pin "1A") (pinfunction "P$1_1A") (pintype "bidirectional"))
      (node (ref "CP1") (pin "1B") (pinfunction "P$1_1B") (pintype "bidirectional"))
      (node (ref "PAD10") (pin "TP") (pinfunction "TP_TP") (pintype "input"))
      (node (ref "PAD11") (pin "TP") (pinfunction "TP_TP") (pintype "input"))
      (node (ref "PAD12") (pin "TP") (pinfunction "TP_TP") (pintype "input"))
      (node (ref "PAD9") (pin "TP") (pinfunction "TP_TP") (pintype "input"))
      (node (ref "TP1") (pin "P$1") (pinfunction "P$1_P$1") (pintype "bidirectional"))
    )
    (net (code "88") (name "SAO{slash}SDO{slash}ADDR") (class "Default")
      (node (ref "U8") (pin "7") (pinfunction "SA0/SDO_7") (pintype "bidirectional"))
    )
    (net (code "89") (name "VBUS-C") (class "Default")
      (node (ref "D1") (pin "A") (pinfunction "A_A") (pintype "passive"))
      (node (ref "FB5") (pin "2") (pinfunction "2_2") (pintype "bidirectional"))
      (node (ref "Q2") (pin "5") (pinfunction "D_5") (pintype "passive"))
      (node (ref "Q2") (pin "6") (pinfunction "D_6") (pintype "passive"))
      (node (ref "Q2") (pin "7") (pinfunction "D_7") (pintype "passive"))
      (node (ref "Q2") (pin "8") (pinfunction "D_8") (pintype "passive"))
      (node (ref "Q2") (pin "9") (pinfunction "D_9") (pintype "passive"))
      (node (ref "R10") (pin "1") (pinfunction "1_1") (pintype "passive"))
      (node (ref "R24") (pin "1") (pinfunction "1_1") (pintype "passive"))
      (node (ref "R37") (pin "2") (pinfunction "2_2") (pintype "passive"))
    )
    (net (code "90") (name "unconnected-(J3-SBU1-PadA8)") (class "Default")
      (node (ref "J3") (pin "A8") (pinfunction "SBU1_A8") (pintype "bidirectional"))
    )
    (net (code "91") (name "unconnected-(J3-SBU2-PadB8)") (class "Default")
      (node (ref "J3") (pin "B8") (pinfunction "SBU2_B8") (pintype "bidirectional"))
    )
    (net (code "92") (name "unconnected-(U1-VCONN_01-Pad12)") (class "Default")
      (node (ref "U1") (pin "12") (pinfunction "VCONN_01_12") (pintype "bidirectional"))
    )
    (net (code "93") (name "unconnected-(U1-VCONN_02-Pad13)") (class "Default")
      (node (ref "U1") (pin "13") (pinfunction "VCONN_02_13") (pintype "bidirectional"))
    )
    (net (code "94") (name "unconnected-(VD1-P$5-Pad5)") (class "Default")
      (node (ref "VD1") (pin "5") (pinfunction "P$5_5") (pintype "bidirectional"))
    )
  )
)
